# GDE043A2_FeatherWing.net
KiCad netlist of a schematic drawn in EAGLE
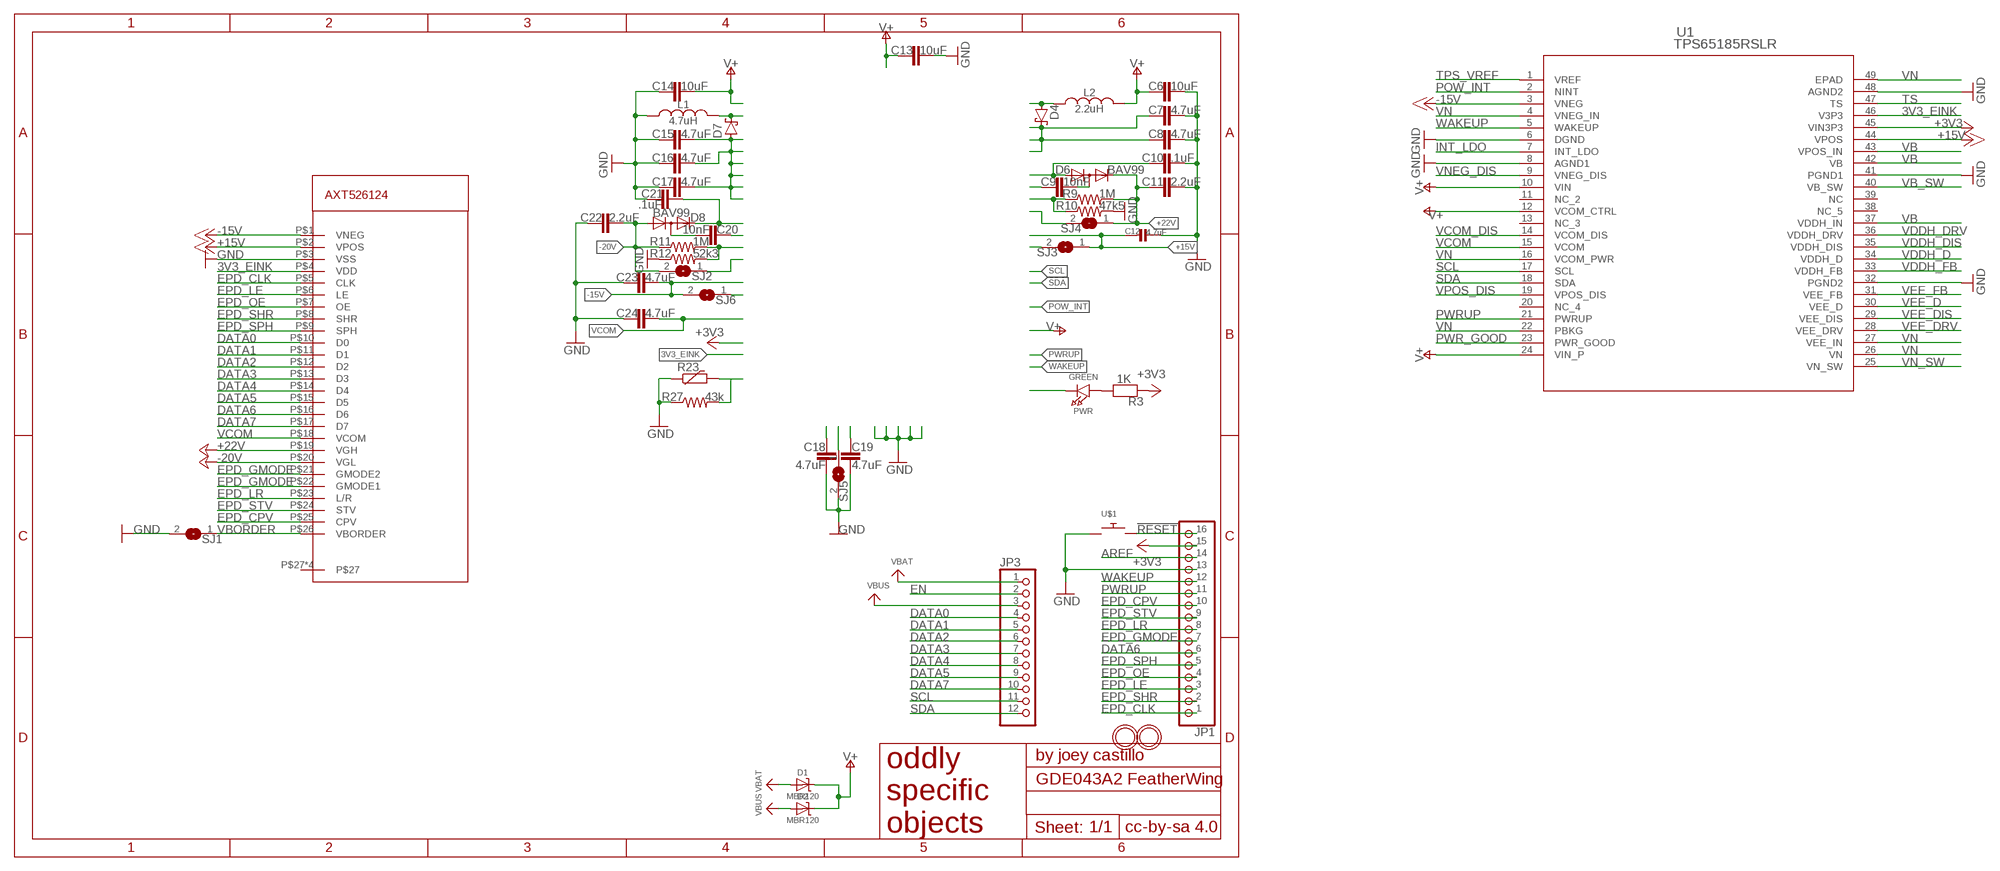
[diagram p0: schematic, sheet 1]

(export (version "E")
  (design (tool "Eeschema 10.0.6"))
  (components
    (comp (ref "C6")
      (value "10uF")
      (footprint "eagle-import:C0805K")
      (libsource (lib "eagle-import") (part "C-EUC0805K"))
    )
    (comp (ref "C7")
      (value "4.7uF")
      (footprint "eagle-import:C0805K")
      (libsource (lib "eagle-import") (part "C-EUC0805K"))
    )
    (comp (ref "C8")
      (value "4.7uF")
      (footprint "eagle-import:C0805K")
      (libsource (lib "eagle-import") (part "C-EUC0805K"))
    )
    (comp (ref "C9")
      (value "10nF")
      (footprint "eagle-import:C0805K")
      (libsource (lib "eagle-import") (part "C-EUC0805K"))
    )
    (comp (ref "C10")
      (value ".1uF")
      (footprint "eagle-import:C0805K")
      (libsource (lib "eagle-import") (part "C-EUC0805K"))
    )
    (comp (ref "C11")
      (value "2.2uF")
      (footprint "eagle-import:C0805K")
      (libsource (lib "eagle-import") (part "C-EUC0805K"))
    )
    (comp (ref "C12")
      (value "4.7uF")
      (footprint "eagle-import:0805_10MGAP")
      (libsource (lib "eagle-import") (part "CAP_CERAMIC0805_10MGAP"))
    )
    (comp (ref "C13")
      (value "10uF")
      (footprint "eagle-import:C0805K")
      (libsource (lib "eagle-import") (part "C-EUC0805K"))
    )
    (comp (ref "C14")
      (value "10uF")
      (footprint "eagle-import:C0805K")
      (libsource (lib "eagle-import") (part "C-EUC0805K"))
    )
    (comp (ref "C15")
      (value "4.7uF")
      (footprint "eagle-import:C0805K")
      (libsource (lib "eagle-import") (part "C-EUC0805K"))
    )
    (comp (ref "C16")
      (value "4.7uF")
      (footprint "eagle-import:C0805K")
      (libsource (lib "eagle-import") (part "C-EUC0805K"))
    )
    (comp (ref "C17")
      (value "4.7uF")
      (footprint "eagle-import:C0805K")
      (libsource (lib "eagle-import") (part "C-EUC0805K"))
    )
    (comp (ref "C18")
      (value "4.7uF")
      (footprint "eagle-import:C0805K")
      (libsource (lib "eagle-import") (part "C-EUC0805K"))
    )
    (comp (ref "C19")
      (value "4.7uF")
      (footprint "eagle-import:C0805K")
      (libsource (lib "eagle-import") (part "C-EUC0805K"))
    )
    (comp (ref "C20")
      (value "10nF")
      (footprint "eagle-import:C0805K")
      (libsource (lib "eagle-import") (part "C-EUC0805K"))
    )
    (comp (ref "C21")
      (value ".1uF")
      (footprint "eagle-import:C0805K")
      (libsource (lib "eagle-import") (part "C-EUC0805K"))
    )
    (comp (ref "C22")
      (value "2.2uF")
      (footprint "eagle-import:C0805K")
      (libsource (lib "eagle-import") (part "C-EUC0805K"))
    )
    (comp (ref "C23")
      (value "4.7uF")
      (footprint "eagle-import:C0805K")
      (libsource (lib "eagle-import") (part "C-EUC0805K"))
    )
    (comp (ref "C24")
      (value "4.7uF")
      (footprint "eagle-import:C0805K")
      (libsource (lib "eagle-import") (part "C-EUC0805K"))
    )
    (comp (ref "D1")
      (value "MBR120")
      (footprint "eagle-import:SOD-123")
      (libsource (lib "eagle-import") (part "DIODE-SCHOTTKYSOD-123"))
    )
    (comp (ref "D2")
      (value "MBR120")
      (footprint "eagle-import:SOD-123")
      (libsource (lib "eagle-import") (part "DIODE-SCHOTTKYSOD-123"))
    )
    (comp (ref "D4")
      (value "MBR130T3G")
      (footprint "eagle-import:SOD123")
      (libsource (lib "eagle-import") (part "MBR130T3G"))
    )
    (comp (ref "D6")
      (value "BAV99")
      (footprint "eagle-import:SOT23")
      (libsource (lib "eagle-import") (part "BAV199"))
    )
    (comp (ref "D7")
      (value "MBR130T3G")
      (footprint "eagle-import:SOD123")
      (libsource (lib "eagle-import") (part "MBR130T3G"))
    )
    (comp (ref "D8")
      (value "BAV99")
      (footprint "eagle-import:SOT23")
      (libsource (lib "eagle-import") (part "BAV199"))
    )
    (comp (ref "JP1")
      (value "HEADER-1X16_MIN")
      (footprint "eagle-import:1X16_ROUND_MIN")
      (libsource (lib "eagle-import") (part "HEADER-1X16_MIN"))
    )
    (comp (ref "JP3")
      (value "HEADER-1X12_MIN")
      (footprint "eagle-import:1X12_ROUND_MIN")
      (libsource (lib "eagle-import") (part "HEADER-1X12_MIN"))
    )
    (comp (ref "L1")
      (value "4.7uH")
      (footprint "eagle-import:NR4012")
      (libsource (lib "eagle-import") (part "NR4012"))
    )
    (comp (ref "L2")
      (value "2.2uH")
      (footprint "eagle-import:NR4012")
      (libsource (lib "eagle-import") (part "NR4012"))
    )
    (comp (ref "PWR")
      (value "GREEN")
      (footprint "eagle-import:CHIPLED_0805_NOOUTLINE")
      (libsource (lib "eagle-import") (part "LED0805_NOOUTLINE"))
    )
    (comp (ref "R3")
      (value "1K")
      (footprint "eagle-import:0805-NO")
      (libsource (lib "eagle-import") (part "RESISTOR0805_NOOUTLINE"))
    )
    (comp (ref "R9")
      (value "1M")
      (footprint "eagle-import:R0805")
      (libsource (lib "eagle-import") (part "R-US_R0805"))
    )
    (comp (ref "R10")
      (value "47k5")
      (footprint "eagle-import:R0805")
      (libsource (lib "eagle-import") (part "R-US_R0805"))
    )
    (comp (ref "R11")
      (value "1M")
      (footprint "eagle-import:R0805")
      (libsource (lib "eagle-import") (part "R-US_R0805"))
    )
    (comp (ref "R12")
      (value "52k3")
      (footprint "eagle-import:R0805")
      (libsource (lib "eagle-import") (part "R-US_R0805"))
    )
    (comp (ref "R23")
      (value "R-EU_R0805")
      (footprint "eagle-import:R0805")
      (libsource (lib "eagle-import") (part "R-EU_R0805"))
    )
    (comp (ref "R27")
      (value "43k")
      (footprint "eagle-import:R0805")
      (libsource (lib "eagle-import") (part "R-US_R0805"))
    )
    (comp (ref "SJ1") (value "SJ") (footprint "eagle-import:SJ") (libsource (lib "eagle-import") (part "SJ")))
    (comp (ref "SJ2") (value "SJ") (footprint "eagle-import:SJ") (libsource (lib "eagle-import") (part "SJ")))
    (comp (ref "SJ3") (value "SJ") (footprint "eagle-import:SJ") (libsource (lib "eagle-import") (part "SJ")))
    (comp (ref "SJ4") (value "SJ") (footprint "eagle-import:SJ") (libsource (lib "eagle-import") (part "SJ")))
    (comp (ref "SJ5") (value "SJ") (footprint "eagle-import:SJ") (libsource (lib "eagle-import") (part "SJ")))
    (comp (ref "SJ6") (value "SJ") (footprint "eagle-import:SJ") (libsource (lib "eagle-import") (part "SJ")))
    (comp (ref "U$1")
      (value "SPST_TACTILE_SWITCHTHRU-SECONDTRY")
      (footprint "eagle-import:MJTP1250-TRY2")
      (libsource (lib "eagle-import") (part "SPST_TACTILE_SWITCHTHRU-SECONDTRY"))
    )
    (comp (ref "U$2")
      (value "AXT526124")
      (footprint "eagle-import:AXT526124")
      (libsource (lib "eagle-import") (part "AXT526124"))
    )
    (comp (ref "U$31")
      (value "MOUNTINGHOLE2.5")
      (footprint "eagle-import:MOUNTINGHOLE_2.5_PLATED")
      (libsource (lib "eagle-import") (part "MOUNTINGHOLE2.5"))
    )
    (comp (ref "U$32")
      (value "MOUNTINGHOLE2.5")
      (footprint "eagle-import:MOUNTINGHOLE_2.5_PLATED")
      (libsource (lib "eagle-import") (part "MOUNTINGHOLE2.5"))
    )
    (comp (ref "U1")
      (value "TPS65185RSLR")
      (footprint "eagle-import:RSL48_4P4X4P4")
      (fields (field (name "MANUFACTURER") "Texas Instruments"))
      (libsource (lib "eagle-import") (part "TPS65185RSLR"))
    )
  )
  (nets
    (net (code "1") (name "+3V3") (class "Default")
      (node (ref "JP1") (pin "15") (pinfunction "15_15") (pintype "passive"))
      (node (ref "R3") (pin "1") (pinfunction "1_1") (pintype "passive"))
      (node (ref "U1") (pin "45") (pinfunction "VIN3P3_45") (pintype "input"))
    )
    (net (code "2") (name "+15V") (class "Default")
      (node (ref "C12") (pin "2") (pinfunction "2_2") (pintype "passive"))
      (node (ref "SJ3") (pin "1") (pinfunction "1_1") (pintype "passive"))
      (node (ref "U$2") (pin "P$2") (pinfunction "VPOS_P$2") (pintype "bidirectional"))
      (node (ref "U1") (pin "44") (pinfunction "VPOS_44") (pintype "output"))
    )
    (net (code "3") (name "+22V") (class "Default")
      (node (ref "C11") (pin "1") (pinfunction "1_1") (pintype "passive"))
      (node (ref "D6") (pin "2") (pinfunction "C_2") (pintype "passive"))
      (node (ref "R9") (pin "2") (pinfunction "2_2") (pintype "passive"))
      (node (ref "SJ4") (pin "1") (pinfunction "1_1") (pintype "passive"))
      (node (ref "U$2") (pin "P$19") (pinfunction "VGH_P$19") (pintype "bidirectional"))
    )
    (net (code "4") (name "-15V") (class "Default")
      (node (ref "C23") (pin "2") (pinfunction "2_2") (pintype "passive"))
      (node (ref "SJ6") (pin "2") (pinfunction "2_2") (pintype "passive"))
      (node (ref "U$2") (pin "P$1") (pinfunction "VNEG_P$1") (pintype "bidirectional"))
      (node (ref "U1") (pin "3") (pinfunction "VNEG_3") (pintype "output"))
    )
    (net (code "5") (name "-20V") (class "Default")
      (node (ref "C22") (pin "2") (pinfunction "2_2") (pintype "passive"))
      (node (ref "D8") (pin "1") (pinfunction "A_1") (pintype "passive"))
      (node (ref "R11") (pin "1") (pinfunction "1_1") (pintype "passive"))
      (node (ref "SJ2") (pin "2") (pinfunction "2_2") (pintype "passive"))
      (node (ref "U$2") (pin "P$20") (pinfunction "VGL_P$20") (pintype "bidirectional"))
    )
    (net (code "6") (name "/AREF") (class "Default")
      (node (ref "JP1") (pin "14") (pinfunction "14_14") (pintype "passive"))
    )
    (net (code "7") (name "/DATA0") (class "Default")
      (node (ref "JP3") (pin "4") (pinfunction "4_4") (pintype "passive"))
      (node (ref "U$2") (pin "P$10") (pinfunction "D0_P$10") (pintype "bidirectional"))
    )
    (net (code "8") (name "/DATA1") (class "Default")
      (node (ref "JP3") (pin "5") (pinfunction "5_5") (pintype "passive"))
      (node (ref "U$2") (pin "P$11") (pinfunction "D1_P$11") (pintype "bidirectional"))
    )
    (net (code "9") (name "/DATA2") (class "Default")
      (node (ref "JP3") (pin "6") (pinfunction "6_6") (pintype "passive"))
      (node (ref "U$2") (pin "P$12") (pinfunction "D2_P$12") (pintype "bidirectional"))
    )
    (net (code "10") (name "/DATA3") (class "Default")
      (node (ref "JP3") (pin "7") (pinfunction "7_7") (pintype "passive"))
      (node (ref "U$2") (pin "P$13") (pinfunction "D3_P$13") (pintype "bidirectional"))
    )
    (net (code "11") (name "/DATA4") (class "Default")
      (node (ref "JP3") (pin "8") (pinfunction "8_8") (pintype "passive"))
      (node (ref "U$2") (pin "P$14") (pinfunction "D4_P$14") (pintype "bidirectional"))
    )
    (net (code "12") (name "/DATA5") (class "Default")
      (node (ref "JP3") (pin "9") (pinfunction "9_9") (pintype "passive"))
      (node (ref "U$2") (pin "P$15") (pinfunction "D5_P$15") (pintype "bidirectional"))
    )
    (net (code "13") (name "/DATA6") (class "Default")
      (node (ref "JP1") (pin "6") (pinfunction "6_6") (pintype "passive"))
      (node (ref "U$2") (pin "P$16") (pinfunction "D6_P$16") (pintype "bidirectional"))
    )
    (net (code "14") (name "/DATA7") (class "Default")
      (node (ref "JP3") (pin "10") (pinfunction "10_10") (pintype "passive"))
      (node (ref "U$2") (pin "P$17") (pinfunction "D7_P$17") (pintype "bidirectional"))
    )
    (net (code "15") (name "/EN") (class "Default")
      (node (ref "JP3") (pin "2") (pinfunction "2_2") (pintype "passive"))
    )
    (net (code "16") (name "/EPD_CLK") (class "Default")
      (node (ref "JP1") (pin "1") (pinfunction "1_1") (pintype "passive"))
      (node (ref "U$2") (pin "P$5") (pinfunction "CLK_P$5") (pintype "bidirectional"))
    )
    (net (code "17") (name "/EPD_CPV") (class "Default")
      (node (ref "JP1") (pin "10") (pinfunction "10_10") (pintype "passive"))
      (node (ref "U$2") (pin "P$25") (pinfunction "CPV_P$25") (pintype "bidirectional"))
    )
    (net (code "18") (name "/EPD_GMODE") (class "Default")
      (node (ref "JP1") (pin "7") (pinfunction "7_7") (pintype "passive"))
      (node (ref "U$2") (pin "P$21") (pinfunction "GMODE2_P$21") (pintype "bidirectional"))
      (node (ref "U$2") (pin "P$22") (pinfunction "GMODE1_P$22") (pintype "bidirectional"))
    )
    (net (code "19") (name "/EPD_LE") (class "Default")
      (node (ref "JP1") (pin "3") (pinfunction "3_3") (pintype "passive"))
      (node (ref "U$2") (pin "P$6") (pinfunction "LE_P$6") (pintype "bidirectional"))
    )
    (net (code "20") (name "/EPD_LR") (class "Default")
      (node (ref "JP1") (pin "8") (pinfunction "8_8") (pintype "passive"))
      (node (ref "U$2") (pin "P$23") (pinfunction "L/R_P$23") (pintype "bidirectional"))
    )
    (net (code "21") (name "/EPD_OE") (class "Default")
      (node (ref "JP1") (pin "4") (pinfunction "4_4") (pintype "passive"))
      (node (ref "U$2") (pin "P$7") (pinfunction "OE_P$7") (pintype "bidirectional"))
    )
    (net (code "22") (name "/EPD_SHR") (class "Default")
      (node (ref "JP1") (pin "2") (pinfunction "2_2") (pintype "passive"))
      (node (ref "U$2") (pin "P$8") (pinfunction "SHR_P$8") (pintype "bidirectional"))
    )
    (net (code "23") (name "/EPD_SPH") (class "Default")
      (node (ref "JP1") (pin "5") (pinfunction "5_5") (pintype "passive"))
      (node (ref "U$2") (pin "P$9") (pinfunction "SPH_P$9") (pintype "bidirectional"))
    )
    (net (code "24") (name "/EPD_STV") (class "Default")
      (node (ref "JP1") (pin "9") (pinfunction "9_9") (pintype "passive"))
      (node (ref "U$2") (pin "P$24") (pinfunction "STV_P$24") (pintype "bidirectional"))
    )
    (net (code "25") (name "/INT_LDO") (class "Default")
      (node (ref "C18") (pin "2") (pinfunction "2_2") (pintype "passive"))
      (node (ref "U1") (pin "7") (pinfunction "INT_LDO_7") (pintype "output"))
    )
    (net (code "26") (name "/PWR_GOOD") (class "Default")
      (node (ref "PWR") (pin "C") (pinfunction "C_C") (pintype "passive"))
      (node (ref "U1") (pin "23") (pinfunction "PWR_GOOD_23") (pintype "output"))
    )
    (net (code "27") (name "/TPS_VREF") (class "Default")
      (node (ref "C19") (pin "2") (pinfunction "2_2") (pintype "passive"))
      (node (ref "U1") (pin "1") (pinfunction "VREF_1") (pintype "output"))
    )
    (net (code "28") (name "/TS") (class "Default")
      (node (ref "R23") (pin "2") (pinfunction "2_2") (pintype "passive"))
      (node (ref "R27") (pin "2") (pinfunction "2_2") (pintype "passive"))
      (node (ref "U1") (pin "47") (pinfunction "TS_47") (pintype "input"))
    )
    (net (code "29") (name "/VB") (class "Default")
      (node (ref "C7") (pin "1") (pinfunction "1_1") (pintype "passive"))
      (node (ref "C8") (pin "1") (pinfunction "1_1") (pintype "passive"))
      (node (ref "D4") (pin "1") (pinfunction "C_1") (pintype "passive"))
      (node (ref "U1") (pin "37") (pinfunction "VDDH_IN_37") (pintype "input"))
      (node (ref "U1") (pin "42") (pinfunction "VB_42") (pintype "input"))
      (node (ref "U1") (pin "43") (pinfunction "VPOS_IN_43") (pintype "input"))
    )
    (net (code "30") (name "/VBORDER") (class "Default")
      (node (ref "SJ1") (pin "1") (pinfunction "1_1") (pintype "passive"))
      (node (ref "U$2") (pin "P$26") (pinfunction "VBORDER_P$26") (pintype "bidirectional"))
    )
    (net (code "31") (name "/VB_SW") (class "Default")
      (node (ref "D4") (pin "2") (pinfunction "A_2") (pintype "passive"))
      (node (ref "L2") (pin "P$1") (pinfunction "P$1_P$1") (pintype "bidirectional"))
      (node (ref "U1") (pin "40") (pinfunction "VB_SW_40") (pintype "output"))
    )
    (net (code "32") (name "/VCOM_DIS") (class "Default")
      (node (ref "SJ5") (pin "1") (pinfunction "1_1") (pintype "passive"))
      (node (ref "U1") (pin "14") (pinfunction "VCOM_DIS_14") (pintype "input"))
    )
    (net (code "33") (name "/VDDH_D") (class "Default")
      (node (ref "C10") (pin "1") (pinfunction "1_1") (pintype "passive"))
      (node (ref "D6") (pin "1") (pinfunction "A_1") (pintype "passive"))
      (node (ref "U1") (pin "34") (pinfunction "VDDH_D_34") (pintype "output"))
    )
    (net (code "34") (name "/VDDH_DIS") (class "Default")
      (node (ref "SJ4") (pin "2") (pinfunction "2_2") (pintype "passive"))
      (node (ref "U1") (pin "35") (pinfunction "VDDH_DIS_35") (pintype "input"))
    )
    (net (code "35") (name "/VDDH_DRV") (class "Default")
      (node (ref "C9") (pin "1") (pinfunction "1_1") (pintype "passive"))
      (node (ref "U1") (pin "36") (pinfunction "VDDH_DRV_36") (pintype "output"))
    )
    (net (code "36") (name "/VDDH_FB") (class "Default")
      (node (ref "R10") (pin "1") (pinfunction "1_1") (pintype "passive"))
      (node (ref "R9") (pin "1") (pinfunction "1_1") (pintype "passive"))
      (node (ref "U1") (pin "33") (pinfunction "VDDH_FB_33") (pintype "input"))
    )
    (net (code "37") (name "/VEE_D") (class "Default")
      (node (ref "C21") (pin "2") (pinfunction "2_2") (pintype "passive"))
      (node (ref "D8") (pin "2") (pinfunction "C_2") (pintype "passive"))
      (node (ref "U1") (pin "30") (pinfunction "VEE_D_30") (pintype "output"))
    )
    (net (code "38") (name "/VEE_DIS") (class "Default")
      (node (ref "SJ2") (pin "1") (pinfunction "1_1") (pintype "passive"))
      (node (ref "U1") (pin "29") (pinfunction "VEE_DIS_29") (pintype "input"))
    )
    (net (code "39") (name "/VEE_DRV") (class "Default")
      (node (ref "C20") (pin "1") (pinfunction "1_1") (pintype "passive"))
      (node (ref "U1") (pin "28") (pinfunction "VEE_DRV_28") (pintype "output"))
    )
    (net (code "40") (name "/VEE_FB") (class "Default")
      (node (ref "R11") (pin "2") (pinfunction "2_2") (pintype "passive"))
      (node (ref "R12") (pin "2") (pinfunction "2_2") (pintype "passive"))
      (node (ref "U1") (pin "31") (pinfunction "VEE_FB_31") (pintype "input"))
    )
    (net (code "41") (name "/VN") (class "Default")
      (node (ref "C15") (pin "2") (pinfunction "2_2") (pintype "passive"))
      (node (ref "C16") (pin "2") (pinfunction "2_2") (pintype "passive"))
      (node (ref "C17") (pin "2") (pinfunction "2_2") (pintype "passive"))
      (node (ref "D7") (pin "2") (pinfunction "A_2") (pintype "passive"))
      (node (ref "U1") (pin "16") (pinfunction "VCOM_PWR_16") (pintype "input"))
      (node (ref "U1") (pin "22") (pinfunction "PBKG_22") (pintype "passive"))
      (node (ref "U1") (pin "26") (pinfunction "VN_26") (pintype "input"))
      (node (ref "U1") (pin "27") (pinfunction "VEE_IN_27") (pintype "input"))
      (node (ref "U1") (pin "4") (pinfunction "VNEG_IN_4") (pintype "input"))
      (node (ref "U1") (pin "49") (pinfunction "EPAD_49") (pintype "passive"))
    )
    (net (code "42") (name "/VNEG_DIS") (class "Default")
      (node (ref "SJ6") (pin "1") (pinfunction "1_1") (pintype "passive"))
      (node (ref "U1") (pin "9") (pinfunction "VNEG_DIS_9") (pintype "output"))
    )
    (net (code "43") (name "/VN_SW") (class "Default")
      (node (ref "D7") (pin "1") (pinfunction "C_1") (pintype "passive"))
      (node (ref "L1") (pin "P$2") (pinfunction "P$2_P$2") (pintype "bidirectional"))
      (node (ref "U1") (pin "25") (pinfunction "VN_SW_25") (pintype "output"))
    )
    (net (code "44") (name "/VPOS_DIS") (class "Default")
      (node (ref "SJ3") (pin "2") (pinfunction "2_2") (pintype "passive"))
      (node (ref "U1") (pin "19") (pinfunction "VPOS_DIS_19") (pintype "input"))
    )
    (net (code "45") (name "/~{RESET}") (class "Default")
      (node (ref "JP1") (pin "16") (pinfunction "16_16") (pintype "passive"))
      (node (ref "U$1") (pin "P$2") (pinfunction "P$2_P$2") (pintype "passive"))
    )
    (net (code "46") (name "3V3_EINK") (class "Default")
      (node (ref "U$2") (pin "P$4") (pinfunction "VDD_P$4") (pintype "bidirectional"))
      (node (ref "U1") (pin "46") (pinfunction "V3P3_46") (pintype "output"))
    )
    (net (code "47") (name "GND") (class "Default")
      (node (ref "C10") (pin "2") (pinfunction "2_2") (pintype "passive"))
      (node (ref "C11") (pin "2") (pinfunction "2_2") (pintype "passive"))
      (node (ref "C12") (pin "1") (pinfunction "1_1") (pintype "passive"))
      (node (ref "C13") (pin "2") (pinfunction "2_2") (pintype "passive"))
      (node (ref "C14") (pin "1") (pinfunction "1_1") (pintype "passive"))
      (node (ref "C15") (pin "1") (pinfunction "1_1") (pintype "passive"))
      (node (ref "C16") (pin "1") (pinfunction "1_1") (pintype "passive"))
      (node (ref "C17") (pin "1") (pinfunction "1_1") (pintype "passive"))
      (node (ref "C18") (pin "1") (pinfunction "1_1") (pintype "passive"))
      (node (ref "C19") (pin "1") (pinfunction "1_1") (pintype "passive"))
      (node (ref "C21") (pin "1") (pinfunction "1_1") (pintype "passive"))
      (node (ref "C22") (pin "1") (pinfunction "1_1") (pintype "passive"))
      (node (ref "C23") (pin "1") (pinfunction "1_1") (pintype "passive"))
      (node (ref "C24") (pin "1") (pinfunction "1_1") (pintype "passive"))
      (node (ref "C6") (pin "2") (pinfunction "2_2") (pintype "passive"))
      (node (ref "C7") (pin "2") (pinfunction "2_2") (pintype "passive"))
      (node (ref "C8") (pin "2") (pinfunction "2_2") (pintype "passive"))
      (node (ref "JP1") (pin "13") (pinfunction "13_13") (pintype "passive"))
      (node (ref "L1") (pin "P$1") (pinfunction "P$1_P$1") (pintype "bidirectional"))
      (node (ref "R10") (pin "2") (pinfunction "2_2") (pintype "passive"))
      (node (ref "R12") (pin "1") (pinfunction "1_1") (pintype "passive"))
      (node (ref "R23") (pin "1") (pinfunction "1_1") (pintype "passive"))
      (node (ref "R27") (pin "1") (pinfunction "1_1") (pintype "passive"))
      (node (ref "SJ1") (pin "2") (pinfunction "2_2") (pintype "passive"))
      (node (ref "SJ5") (pin "2") (pinfunction "2_2") (pintype "passive"))
      (node (ref "U$1") (pin "P$1") (pinfunction "P$1_P$1") (pintype "passive"))
      (node (ref "U$2") (pin "P$3") (pinfunction "VSS_P$3") (pintype "bidirectional"))
      (node (ref "U1") (pin "32") (pinfunction "PGND2_32") (pintype "power_in"))
      (node (ref "U1") (pin "41") (pinfunction "PGND1_41") (pintype "power_in"))
      (node (ref "U1") (pin "48") (pinfunction "AGND2_48") (pintype "power_in"))
      (node (ref "U1") (pin "6") (pinfunction "DGND_6") (pintype "power_in"))
      (node (ref "U1") (pin "8") (pinfunction "AGND1_8") (pintype "power_in"))
    )
    (net (code "48") (name "Net-(D6-AC)") (class "Default")
      (node (ref "C9") (pin "2") (pinfunction "2_2") (pintype "passive"))
      (node (ref "D6") (pin "3") (pinfunction "AC_3") (pintype "passive"))
    )
    (net (code "49") (name "Net-(D8-AC)") (class "Default")
      (node (ref "C20") (pin "2") (pinfunction "2_2") (pintype "passive"))
      (node (ref "D8") (pin "3") (pinfunction "AC_3") (pintype "passive"))
    )
    (net (code "50") (name "Net-(PWR-PadA)") (class "Default")
      (node (ref "PWR") (pin "A") (pinfunction "A_A") (pintype "passive"))
      (node (ref "R3") (pin "2") (pinfunction "2_2") (pintype "passive"))
    )
    (net (code "51") (name "POW_INT") (class "Default")
      (node (ref "U1") (pin "2") (pinfunction "NINT_2") (pintype "output"))
    )
    (net (code "52") (name "PWRUP") (class "Default")
      (node (ref "JP1") (pin "11") (pinfunction "11_11") (pintype "passive"))
      (node (ref "U1") (pin "21") (pinfunction "PWRUP_21") (pintype "input"))
    )
    (net (code "53") (name "SCL") (class "Default")
      (node (ref "JP3") (pin "11") (pinfunction "11_11") (pintype "passive"))
      (node (ref "U1") (pin "17") (pinfunction "SCL_17") (pintype "input"))
    )
    (net (code "54") (name "SDA") (class "Default")
      (node (ref "JP3") (pin "12") (pinfunction "12_12") (pintype "passive"))
      (node (ref "U1") (pin "18") (pinfunction "SDA_18") (pintype "bidirectional"))
    )
    (net (code "55") (name "V+") (class "Default")
      (node (ref "C13") (pin "1") (pinfunction "1_1") (pintype "passive"))
      (node (ref "C14") (pin "2") (pinfunction "2_2") (pintype "passive"))
      (node (ref "C6") (pin "1") (pinfunction "1_1") (pintype "passive"))
      (node (ref "D1") (pin "C") (pinfunction "C_C") (pintype "passive"))
      (node (ref "D2") (pin "C") (pinfunction "C_C") (pintype "passive"))
      (node (ref "L2") (pin "P$2") (pinfunction "P$2_P$2") (pintype "bidirectional"))
      (node (ref "U1") (pin "10") (pinfunction "VIN_10") (pintype "input"))
      (node (ref "U1") (pin "12") (pinfunction "VCOM_CTRL_12") (pintype "input"))
      (node (ref "U1") (pin "24") (pinfunction "VIN_P_24") (pintype "input"))
    )
    (net (code "56") (name "VBAT") (class "Default")
      (node (ref "D1") (pin "A") (pinfunction "A_A") (pintype "passive"))
      (node (ref "JP3") (pin "1") (pinfunction "1_1") (pintype "passive"))
    )
    (net (code "57") (name "VBUS") (class "Default")
      (node (ref "D2") (pin "A") (pinfunction "A_A") (pintype "passive"))
      (node (ref "JP3") (pin "3") (pinfunction "3_3") (pintype "passive"))
    )
    (net (code "58") (name "VCOM") (class "Default")
      (node (ref "C24") (pin "2") (pinfunction "2_2") (pintype "passive"))
      (node (ref "U$2") (pin "P$18") (pinfunction "VCOM_P$18") (pintype "bidirectional"))
      (node (ref "U1") (pin "15") (pinfunction "VCOM_15") (pintype "output"))
    )
    (net (code "59") (name "WAKEUP") (class "Default")
      (node (ref "JP1") (pin "12") (pinfunction "12_12") (pintype "passive"))
      (node (ref "U1") (pin "5") (pinfunction "WAKEUP_5") (pintype "input"))
    )
    (net (code "60") (name "unconnected-(U$2-P$27-PadP$28)") (class "Default")
      (node (ref "U$2") (pin "P$28") (pinfunction "P$27_P$28") (pintype "no_connect"))
    )
    (net (code "61") (name "unconnected-(U$2-P$27-PadP$29)") (class "Default")
      (node (ref "U$2") (pin "P$29") (pinfunction "P$27_P$29") (pintype "no_connect"))
    )
    (net (code "62") (name "unconnected-(U$2-P$27-PadP$30)") (class "Default")
      (node (ref "U$2") (pin "P$30") (pinfunction "P$27_P$30") (pintype "no_connect"))
    )
    (net (code "63") (name "unconnected-(U$2-PadP$27)") (class "Default")
      (node (ref "U$2") (pin "P$27") (pinfunction "P$27_P$27") (pintype "no_connect"))
    )
    (net (code "64") (name "unconnected-(U1-NC-Pad39)") (class "Default")
      (node (ref "U1") (pin "39") (pinfunction "NC_39") (pintype "passive"))
    )
    (net (code "65") (name "unconnected-(U1-NC_2-Pad11)") (class "Default")
      (node (ref "U1") (pin "11") (pinfunction "NC_2_11") (pintype "passive"))
    )
    (net (code "66") (name "unconnected-(U1-NC_3-Pad13)") (class "Default")
      (node (ref "U1") (pin "13") (pinfunction "NC_3_13") (pintype "passive"))
    )
    (net (code "67") (name "unconnected-(U1-NC_4-Pad20)") (class "Default")
      (node (ref "U1") (pin "20") (pinfunction "NC_4_20") (pintype "passive"))
    )
    (net (code "68") (name "unconnected-(U1-NC_5-Pad38)") (class "Default")
      (node (ref "U1") (pin "38") (pinfunction "NC_5_38") (pintype "passive"))
    )
  )
)
